# EasyEDA_source_schematic.net
KiCad netlist of a schematic drawn in EasyEDA
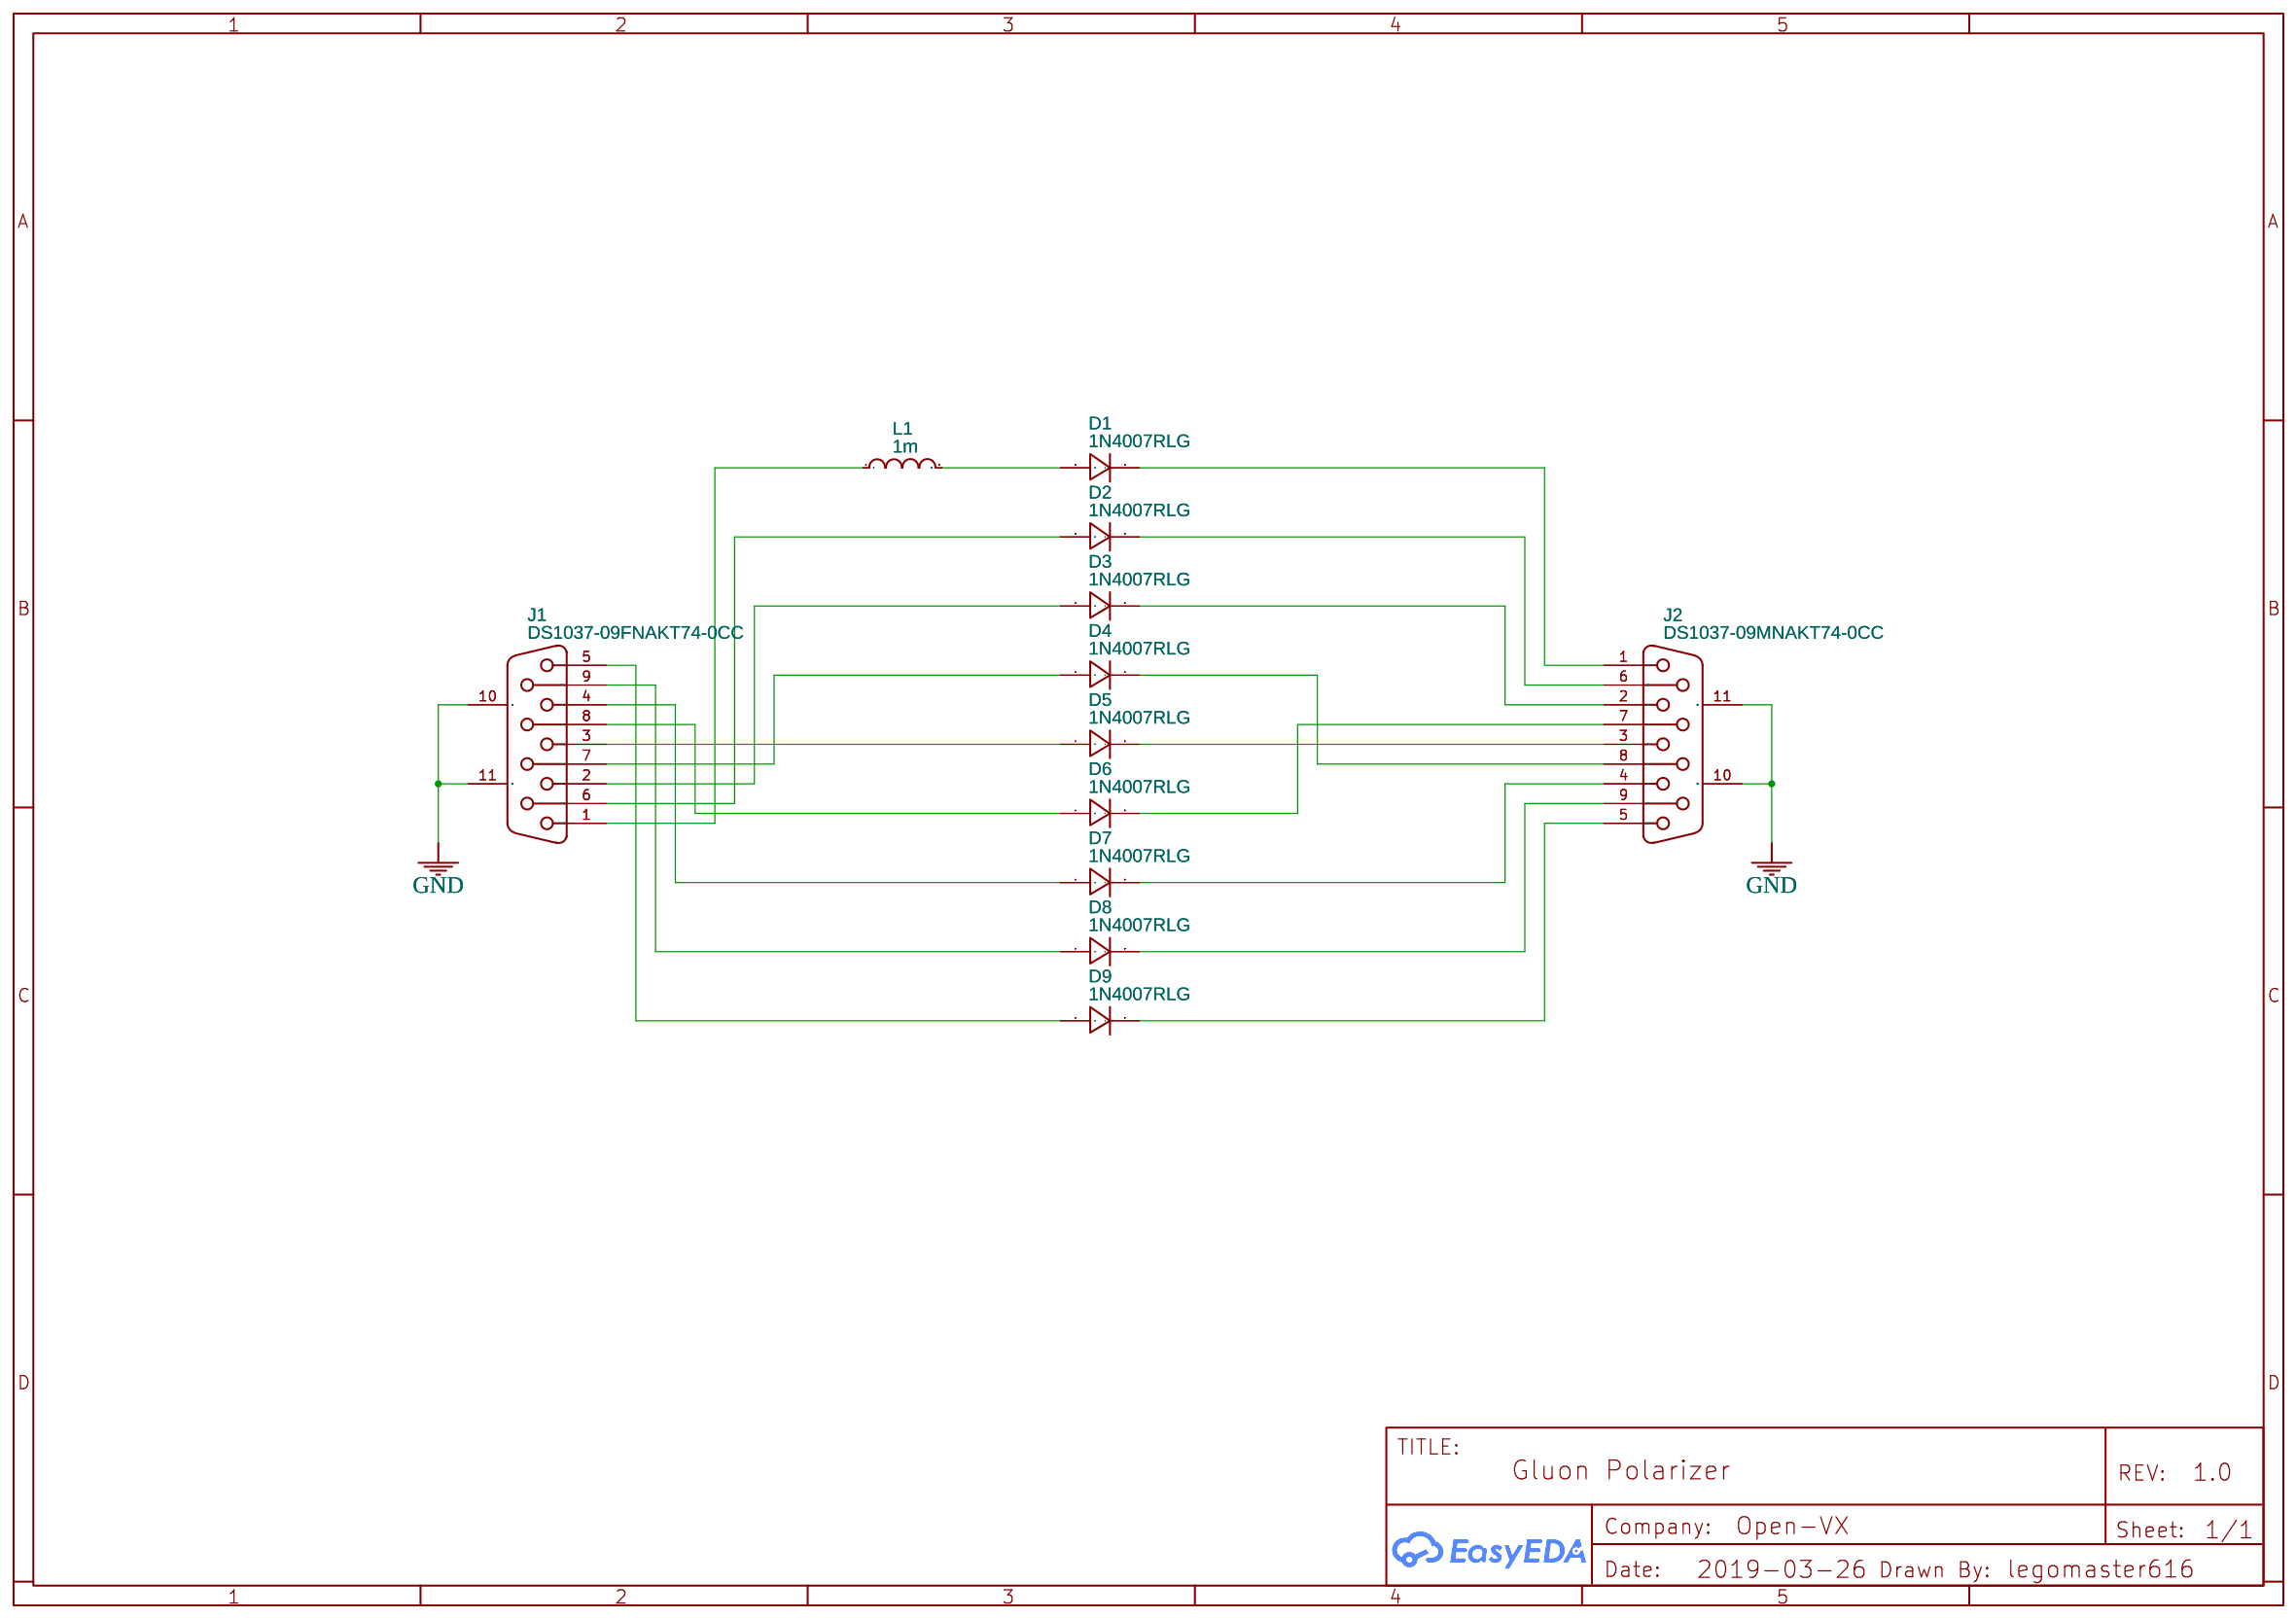
[diagram p0: schematic sheet]

(export (version "E")
  (design (tool "Eeschema 10.0.6"))
  (components
    (comp (ref "D1")
      (value "1N4007RLG")
      (fields (field (name "BOM_Supplier Part") "C53568"))
      (libsource (lib "") (part "Unknown_550_230"))
    )
    (comp (ref "D2")
      (value "1N4007RLG")
      (fields (field (name "BOM_Supplier Part") "C53568"))
      (libsource (lib "") (part "Unknown_550_265"))
    )
    (comp (ref "D3")
      (value "1N4007RLG")
      (fields (field (name "BOM_Supplier Part") "C53568"))
      (libsource (lib "") (part "Unknown_550_300"))
    )
    (comp (ref "D4")
      (value "1N4007RLG")
      (fields (field (name "BOM_Supplier Part") "C53568"))
      (libsource (lib "") (part "Unknown_550_335"))
    )
    (comp (ref "D5")
      (value "1N4007RLG")
      (fields (field (name "BOM_Supplier Part") "C53568"))
      (libsource (lib "") (part "Unknown_550_370"))
    )
    (comp (ref "D6")
      (value "1N4007RLG")
      (fields (field (name "BOM_Supplier Part") "C53568"))
      (libsource (lib "") (part "Unknown_550_405"))
    )
    (comp (ref "D7")
      (value "1N4007RLG")
      (fields (field (name "BOM_Supplier Part") "C53568"))
      (libsource (lib "") (part "Unknown_550_440"))
    )
    (comp (ref "D8")
      (value "1N4007RLG")
      (fields (field (name "BOM_Supplier Part") "C53568"))
      (libsource (lib "") (part "Unknown_550_475"))
    )
    (comp (ref "D9")
      (value "1N4007RLG")
      (fields (field (name "BOM_Supplier Part") "C53568"))
      (libsource (lib "") (part "Unknown_550_510"))
    )
    (comp (ref "J1")
      (value "DS1037-09FNAKT74-0CC")
      (fields (field (name "BOM_Supplier Part") "C75749"))
      (libsource (lib "") (part "Unknown_265_370"))
    )
    (comp (ref "J2")
      (value "DS1037-09MNAKT74-0CC")
      (fields (field (name "BOM_Supplier Part") "C75750"))
      (libsource (lib "") (part "Unknown_840_370"))
    )
    (comp (ref "L1")
      (value "1m")
      (fields (field (name "BOM_Manufacturer Part") "?"))
      (libsource (lib "") (part "Inductor_AXIAL-0.4_US"))
    )
  )
  (nets
    (net (code "1") (name "GND") (class "Default")
      (node (ref "J1") (pin "10") (pinfunction "MH1_10") (pintype "input"))
      (node (ref "J1") (pin "11") (pinfunction "MH2_11") (pintype "input"))
      (node (ref "J2") (pin "10") (pinfunction "MH1_10") (pintype "input"))
      (node (ref "J2") (pin "11") (pinfunction "MH2_11") (pintype "input"))
    )
    (net (code "2") (name "Net-(D1-+)") (class "Default")
      (node (ref "D1") (pin "1") (pinfunction "+_1") (pintype "unspecified"))
      (node (ref "L1") (pin "2") (pinfunction "2_2") (pintype "unspecified"))
    )
    (net (code "3") (name "Net-(D1--)") (class "Default")
      (node (ref "D1") (pin "2") (pinfunction "-_2") (pintype "unspecified"))
      (node (ref "J2") (pin "1") (pinfunction "1_1") (pintype "input"))
    )
    (net (code "4") (name "Net-(D2-+)") (class "Default")
      (node (ref "D2") (pin "1") (pinfunction "+_1") (pintype "unspecified"))
      (node (ref "J1") (pin "6") (pinfunction "6_6") (pintype "input"))
    )
    (net (code "5") (name "Net-(D2--)") (class "Default")
      (node (ref "D2") (pin "2") (pinfunction "-_2") (pintype "unspecified"))
      (node (ref "J2") (pin "6") (pinfunction "6_6") (pintype "input"))
    )
    (net (code "6") (name "Net-(D3-+)") (class "Default")
      (node (ref "D3") (pin "1") (pinfunction "+_1") (pintype "unspecified"))
      (node (ref "J1") (pin "2") (pinfunction "2_2") (pintype "input"))
    )
    (net (code "7") (name "Net-(D3--)") (class "Default")
      (node (ref "D3") (pin "2") (pinfunction "-_2") (pintype "unspecified"))
      (node (ref "J2") (pin "2") (pinfunction "2_2") (pintype "input"))
    )
    (net (code "8") (name "Net-(D4-+)") (class "Default")
      (node (ref "D4") (pin "1") (pinfunction "+_1") (pintype "unspecified"))
      (node (ref "J1") (pin "7") (pinfunction "7_7") (pintype "input"))
    )
    (net (code "9") (name "Net-(D4--)") (class "Default")
      (node (ref "D4") (pin "2") (pinfunction "-_2") (pintype "unspecified"))
      (node (ref "J2") (pin "8") (pinfunction "8_8") (pintype "input"))
    )
    (net (code "10") (name "Net-(D5-+)") (class "Default")
      (node (ref "D5") (pin "1") (pinfunction "+_1") (pintype "unspecified"))
      (node (ref "J1") (pin "3") (pinfunction "3_3") (pintype "input"))
    )
    (net (code "11") (name "Net-(D5--)") (class "Default")
      (node (ref "D5") (pin "2") (pinfunction "-_2") (pintype "unspecified"))
      (node (ref "J2") (pin "3") (pinfunction "3_3") (pintype "input"))
    )
    (net (code "12") (name "Net-(D6-+)") (class "Default")
      (node (ref "D6") (pin "1") (pinfunction "+_1") (pintype "unspecified"))
      (node (ref "J1") (pin "8") (pinfunction "8_8") (pintype "input"))
    )
    (net (code "13") (name "Net-(D6--)") (class "Default")
      (node (ref "D6") (pin "2") (pinfunction "-_2") (pintype "unspecified"))
      (node (ref "J2") (pin "7") (pinfunction "7_7") (pintype "input"))
    )
    (net (code "14") (name "Net-(D7-+)") (class "Default")
      (node (ref "D7") (pin "1") (pinfunction "+_1") (pintype "unspecified"))
      (node (ref "J1") (pin "4") (pinfunction "4_4") (pintype "input"))
    )
    (net (code "15") (name "Net-(D7--)") (class "Default")
      (node (ref "D7") (pin "2") (pinfunction "-_2") (pintype "unspecified"))
      (node (ref "J2") (pin "4") (pinfunction "4_4") (pintype "input"))
    )
    (net (code "16") (name "Net-(D8-+)") (class "Default")
      (node (ref "D8") (pin "1") (pinfunction "+_1") (pintype "unspecified"))
      (node (ref "J1") (pin "9") (pinfunction "9_9") (pintype "input"))
    )
    (net (code "17") (name "Net-(D8--)") (class "Default")
      (node (ref "D8") (pin "2") (pinfunction "-_2") (pintype "unspecified"))
      (node (ref "J2") (pin "9") (pinfunction "9_9") (pintype "input"))
    )
    (net (code "18") (name "Net-(D9-+)") (class "Default")
      (node (ref "D9") (pin "1") (pinfunction "+_1") (pintype "unspecified"))
      (node (ref "J1") (pin "5") (pinfunction "5_5") (pintype "input"))
    )
    (net (code "19") (name "Net-(D9--)") (class "Default")
      (node (ref "D9") (pin "2") (pinfunction "-_2") (pintype "unspecified"))
      (node (ref "J2") (pin "5") (pinfunction "5_5") (pintype "input"))
    )
    (net (code "20") (name "Net-(J1-Pad1)") (class "Default")
      (node (ref "J1") (pin "1") (pinfunction "1_1") (pintype "input"))
      (node (ref "L1") (pin "1") (pinfunction "1_1") (pintype "unspecified"))
    )
  )
)
